# RELAY5.net
KiCad netlist of a schematic drawn in Altium Designer
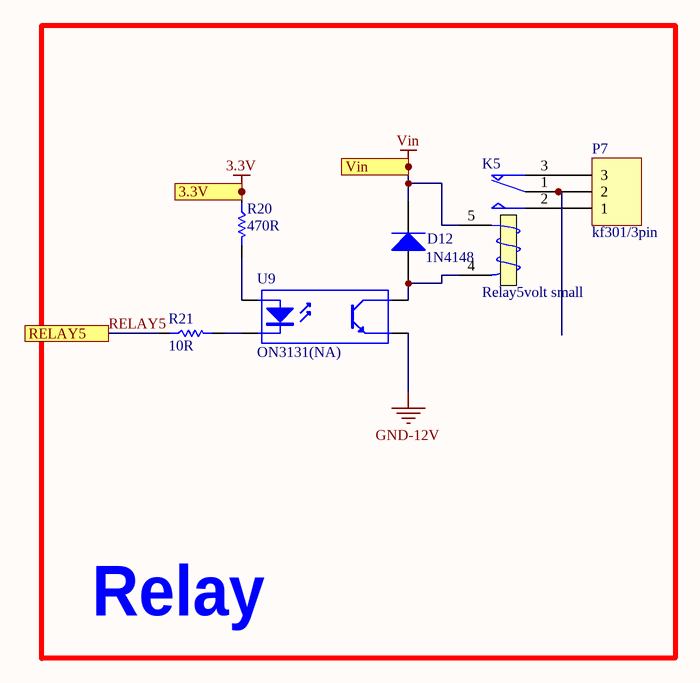
[diagram p0: RELAY5.SchDoc]

(export (version "E")
  (design (tool "Eeschema 10.0.6"))
  (components
    (comp (ref "D12")
      (value "1N4148")
      (footprint "sod123")
      (description "1 Amp General Purpose Rectifier")
      (fields (field (name "PUBLISHER") "Altium Limited"))
      (libsource (lib "Miscellaneous Devices") (part "Diode 1N4007"))
    )
    (comp (ref "K5")
      (value "Relay5volt small")
      (footprint "relay5_childern")
      (description "SPDT Relay")
      (fields (field (name "PUBLISHER") "Altium Limited"))
      (libsource (lib "FLIB") (part "Relay"))
    )
    (comp (ref "P7")
      (value "kf301/3pin")
      (footprint "Blue Connector 1*3 -kf301")
      (fields (field (name "PUBLISHER") "Altium Limited"))
      (libsource (lib "Miscellaneous Connectors") (part "Header 3"))
    )
    (comp (ref "R20")
      (value "470R")
      (footprint "0805/resistor")
      (description "Resistor")
      (fields (field (name "TOLERANCE") "5%") (field (name "POWER") "1/8 W"))
      (libsource (lib "skille") (part "Resistor"))
    )
    (comp (ref "R21")
      (value "10R")
      (footprint "0805/resistor")
      (description "Resistor")
      (fields (field (name "TOLERANCE") "5%") (field (name "POWER") "1/8 W"))
      (libsource (lib "skille") (part "Resistor"))
    )
    (comp (ref "U9")
      (value "ON3131(NA)")
      (footprint "OPTO_COUPLER")
      (description "4-Pin Phototransistor Optocoupler")
      (fields (field (name "PUBLISHER") "Altium Limited"))
      (libsource (lib "skille") (part "Optoisolator1"))
    )
  )
  (nets
    (net (code "1") (name "/RELAY5") (class "Default")
      (node (ref "R21") (pin "1") (pinfunction "1_1") (pintype "passive"))
    )
    (net (code "2") (name "3.3V") (class "Default")
      (node (ref "R20") (pin "1") (pinfunction "1_1") (pintype "passive"))
    )
    (net (code "3") (name "GND-12V") (class "Default")
      (node (ref "U9") (pin "3") (pinfunction "E_3") (pintype "passive"))
    )
    (net (code "4") (name "Net-(K5-COM)") (class "Default")
      (node (ref "K5") (pin "1") (pinfunction "COM_1") (pintype "passive"))
      (node (ref "P7") (pin "2") (pinfunction "2_2") (pintype "passive"))
    )
    (net (code "5") (name "Net-(K5-NO)") (class "Default")
      (node (ref "K5") (pin "2") (pinfunction "NO_2") (pintype "passive"))
      (node (ref "P7") (pin "1") (pinfunction "1_1") (pintype "passive"))
    )
    (net (code "6") (name "Net-(K5-T1)") (class "Default")
      (node (ref "K5") (pin "3") (pinfunction "T1_3") (pintype "passive"))
      (node (ref "P7") (pin "3") (pinfunction "3_3") (pintype "passive"))
    )
    (net (code "7") (name "Net-(K5-T2)") (class "Default")
      (node (ref "D12") (pin "A") (pinfunction "A_A") (pintype "passive"))
      (node (ref "K5") (pin "4") (pinfunction "T2_4") (pintype "passive"))
      (node (ref "U9") (pin "4") (pinfunction "C_4") (pintype "passive"))
    )
    (net (code "8") (name "Net-(U9-A)") (class "Default")
      (node (ref "R20") (pin "2") (pinfunction "2_2") (pintype "passive"))
      (node (ref "U9") (pin "1") (pinfunction "A_1") (pintype "passive"))
    )
    (net (code "9") (name "Net-(U9-K)") (class "Default")
      (node (ref "R21") (pin "2") (pinfunction "2_2") (pintype "passive"))
      (node (ref "U9") (pin "2") (pinfunction "K_2") (pintype "passive"))
    )
    (net (code "10") (name "Vin") (class "Default")
      (node (ref "D12") (pin "K") (pinfunction "K_K") (pintype "passive"))
      (node (ref "K5") (pin "5") (pinfunction "5_5") (pintype "passive"))
    )
  )
)
